# lampuIOT.net
KiCad netlist of a schematic drawn in EAGLE
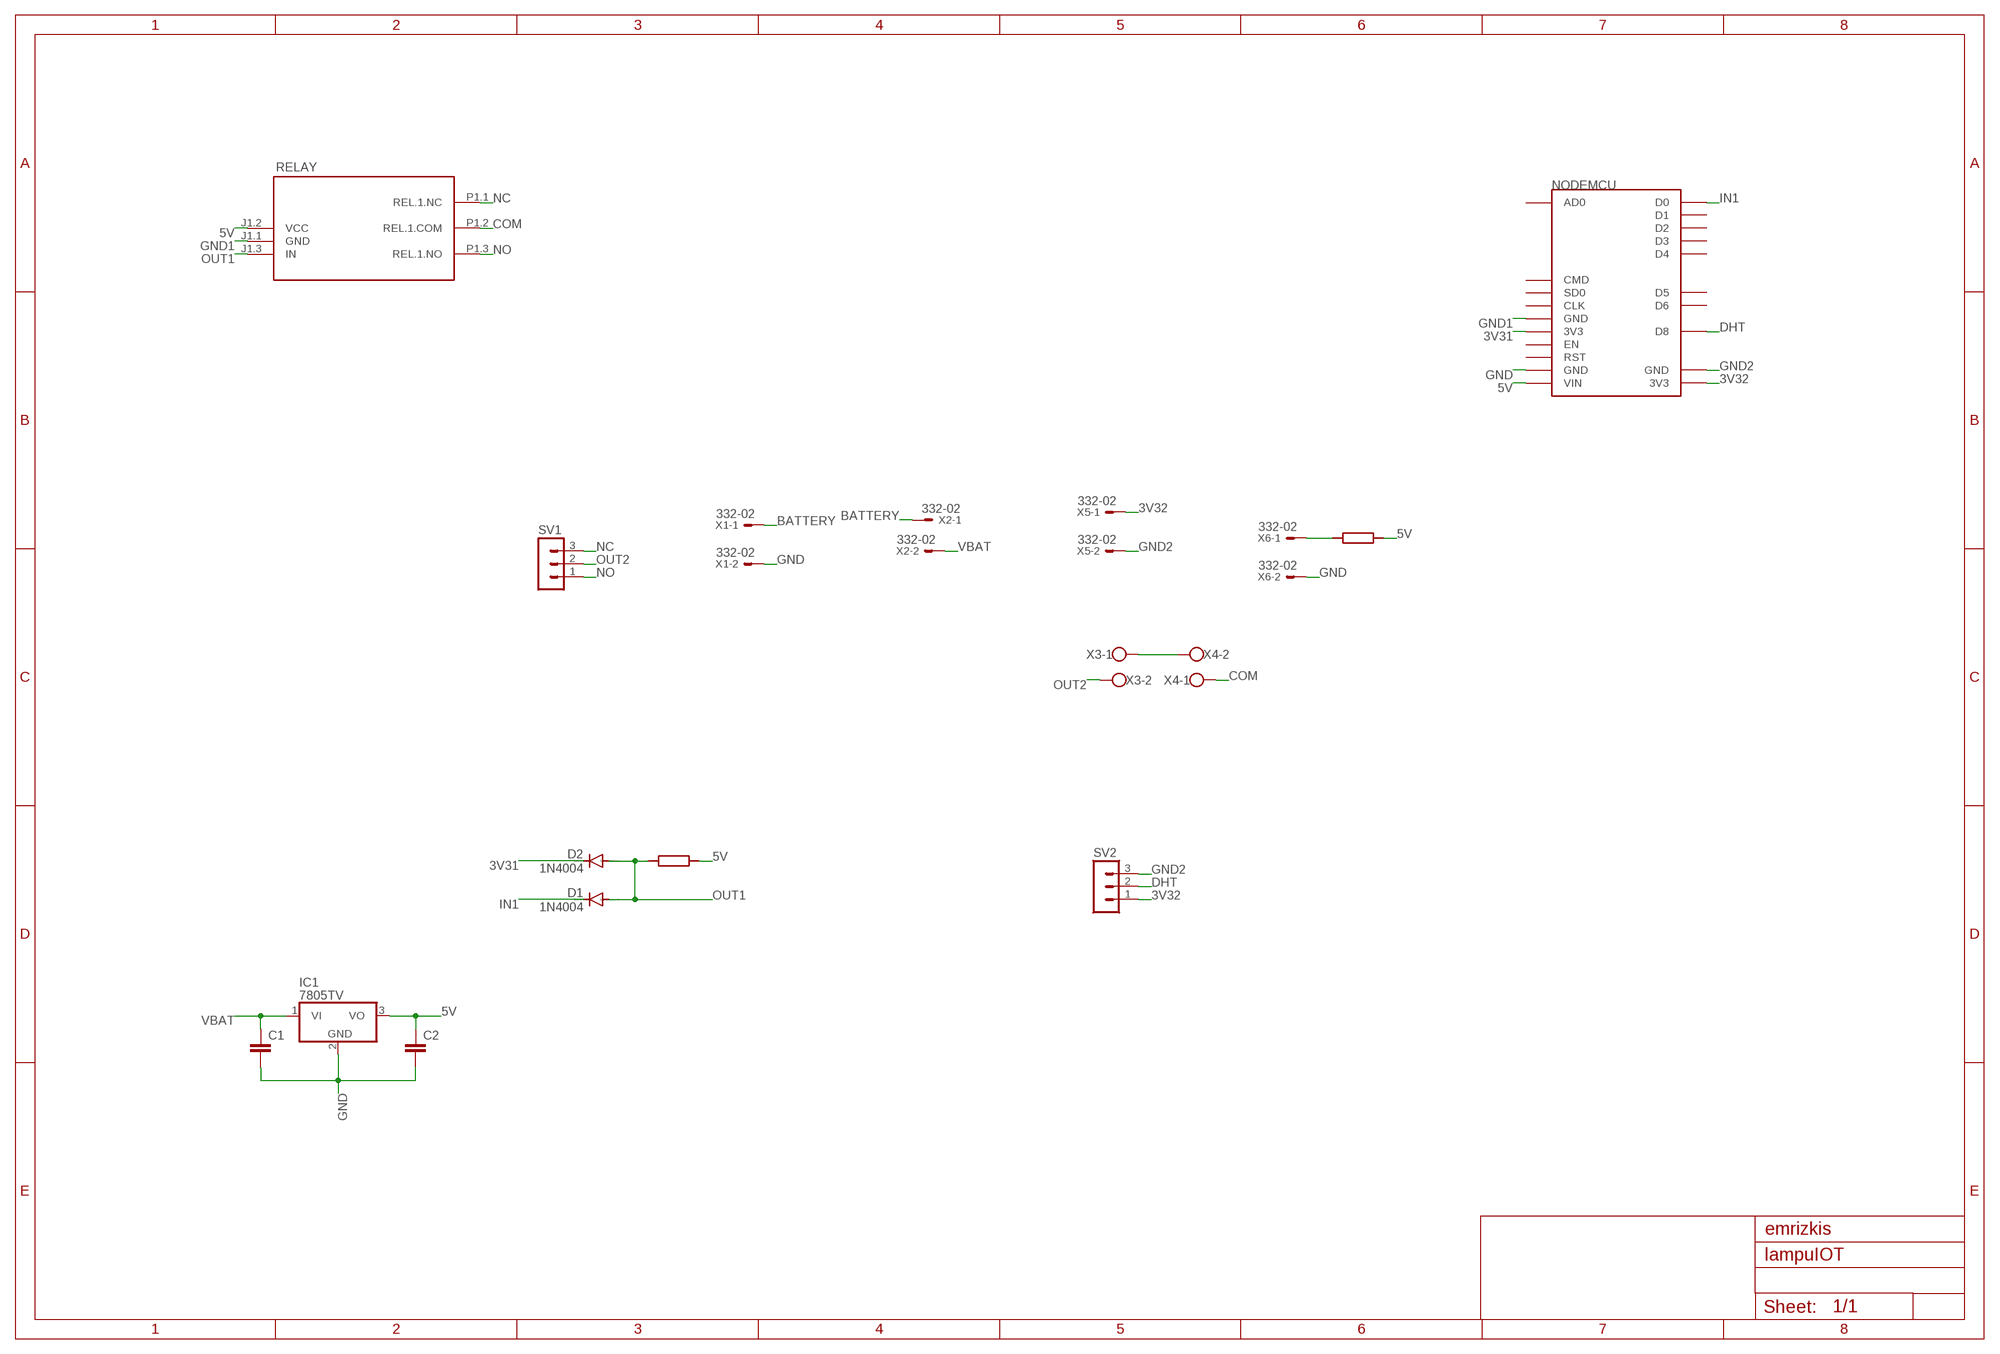
[diagram p0: schematic, sheet 1]

(export (version "E")
  (design (tool "Eeschema 10.0.6"))
  (components
    (comp (ref "C1")
      (value "C2.5/2")
      (footprint "eagle-import:C2.5-2")
      (libsource (lib "eagle-import") (part "C2.5/2"))
    )
    (comp (ref "C2")
      (value "C2.5/2")
      (footprint "eagle-import:C2.5-2")
      (libsource (lib "eagle-import") (part "C2.5/2"))
    )
    (comp (ref "D1")
      (value "1N4004")
      (footprint "eagle-import:DO41-10")
      (libsource (lib "eagle-import") (part "1N4004"))
    )
    (comp (ref "D2")
      (value "1N4004")
      (footprint "eagle-import:DO41-10")
      (libsource (lib "eagle-import") (part "1N4004"))
    )
    (comp (ref "IC1")
      (value "7805TV")
      (footprint "eagle-import:TO220V")
      (libsource (lib "eagle-import") (part "78TV05"))
    )
    (comp (ref "NODEMCU")
      (value "ESP12E_DEVKIT")
      (footprint "eagle-import:ESP12E_DEVKIT")
      (libsource (lib "eagle-import") (part "ESP12E_DEVKIT"))
    )
    (comp (ref "R")
      (value "RESISTOR")
      (footprint "eagle-import:RESISTOR")
      (libsource (lib "eagle-import") (part "RESISTOR"))
    )
    (comp (ref "R1")
      (value "RESISTOR")
      (footprint "eagle-import:RESISTOR")
      (libsource (lib "eagle-import") (part "RESISTOR"))
    )
    (comp (ref "RELAY")
      (value "RELAY1CH")
      (footprint "eagle-import:RELAY1CH")
      (libsource (lib "eagle-import") (part "RELAY1CH"))
    )
    (comp (ref "SV1")
      (value "MA03-1")
      (footprint "eagle-import:MA03-1")
      (libsource (lib "eagle-import") (part "MA03-1"))
    )
    (comp (ref "SV2")
      (value "MA03-1")
      (footprint "eagle-import:MA03-1")
      (libsource (lib "eagle-import") (part "MA03-1"))
    )
    (comp (ref "X1")
      (value "332-02")
      (footprint "eagle-import:332-02")
      (libsource (lib "eagle-import") (part "332-02"))
    )
    (comp (ref "X2")
      (value "332-02")
      (footprint "eagle-import:332-02")
      (libsource (lib "eagle-import") (part "332-02"))
    )
    (comp (ref "X3")
      (value "W237-102")
      (footprint "eagle-import:W237-102")
      (fields (field (name "MPN") "237-102"))
      (libsource (lib "eagle-import") (part "W237-102"))
    )
    (comp (ref "X4")
      (value "W237-102")
      (footprint "eagle-import:W237-102")
      (fields (field (name "MPN") "237-102"))
      (libsource (lib "eagle-import") (part "W237-102"))
    )
    (comp (ref "X5")
      (value "332-02")
      (footprint "eagle-import:332-02")
      (libsource (lib "eagle-import") (part "332-02"))
    )
    (comp (ref "X6")
      (value "332-02")
      (footprint "eagle-import:332-02")
      (libsource (lib "eagle-import") (part "332-02"))
    )
  )
  (nets
    (net (code "1") (name "/3V31") (class "Default")
      (node (ref "D2") (pin "C") (pinfunction "C_C") (pintype "passive"))
      (node (ref "NODEMCU") (pin "3V3@0") (pinfunction "3V3_3V3@0") (pintype "bidirectional"))
    )
    (net (code "2") (name "/3V32") (class "Default")
      (node (ref "NODEMCU") (pin "3V3@2") (pinfunction "3V3_3V3@2") (pintype "bidirectional"))
      (node (ref "SV2") (pin "1") (pinfunction "1_1") (pintype "passive"))
      (node (ref "X5") (pin "1") (pinfunction "S_1") (pintype "passive"))
    )
    (net (code "3") (name "/5V") (class "Default")
      (node (ref "C2") (pin "1") (pinfunction "1_1") (pintype "passive"))
      (node (ref "IC1") (pin "3") (pinfunction "VO_3") (pintype "passive"))
      (node (ref "NODEMCU") (pin "VIN") (pinfunction "VIN_VIN") (pintype "bidirectional"))
      (node (ref "R") (pin "P$1") (pinfunction "1_P$1") (pintype "input"))
      (node (ref "R1") (pin "P$1") (pinfunction "1_P$1") (pintype "input"))
      (node (ref "RELAY") (pin "J1.2") (pinfunction "VCC_J1.2") (pintype "power_in"))
    )
    (net (code "4") (name "/BATTERY") (class "Default")
      (node (ref "X1") (pin "1") (pinfunction "S_1") (pintype "passive"))
      (node (ref "X2") (pin "1") (pinfunction "S_1") (pintype "passive"))
    )
    (net (code "5") (name "/COM") (class "Default")
      (node (ref "RELAY") (pin "P1.2") (pinfunction "REL.1.COM_P1.2") (pintype "bidirectional"))
      (node (ref "X4") (pin "1") (pinfunction "KL_1") (pintype "passive"))
    )
    (net (code "6") (name "/DHT") (class "Default")
      (node (ref "NODEMCU") (pin "D8") (pinfunction "D8_D8") (pintype "bidirectional"))
      (node (ref "SV2") (pin "2") (pinfunction "2_2") (pintype "passive"))
    )
    (net (code "7") (name "/GND") (class "Default")
      (node (ref "C1") (pin "2") (pinfunction "2_2") (pintype "passive"))
      (node (ref "C2") (pin "2") (pinfunction "2_2") (pintype "passive"))
      (node (ref "IC1") (pin "2") (pinfunction "GND_2") (pintype "passive"))
      (node (ref "NODEMCU") (pin "GND@1") (pinfunction "GND_GND@1") (pintype "bidirectional"))
      (node (ref "X1") (pin "2") (pinfunction "S_2") (pintype "passive"))
      (node (ref "X6") (pin "2") (pinfunction "S_2") (pintype "passive"))
    )
    (net (code "8") (name "/GND1") (class "Default")
      (node (ref "NODEMCU") (pin "GND@0") (pinfunction "GND_GND@0") (pintype "bidirectional"))
      (node (ref "RELAY") (pin "J1.1") (pinfunction "GND_J1.1") (pintype "bidirectional"))
    )
    (net (code "9") (name "/GND2") (class "Default")
      (node (ref "NODEMCU") (pin "GND@3") (pinfunction "GND_GND@3") (pintype "bidirectional"))
      (node (ref "SV2") (pin "3") (pinfunction "3_3") (pintype "passive"))
      (node (ref "X5") (pin "2") (pinfunction "S_2") (pintype "passive"))
    )
    (net (code "10") (name "/IN1") (class "Default")
      (node (ref "D1") (pin "C") (pinfunction "C_C") (pintype "passive"))
      (node (ref "NODEMCU") (pin "D0") (pinfunction "D0_D0") (pintype "bidirectional"))
    )
    (net (code "11") (name "/NC") (class "Default")
      (node (ref "RELAY") (pin "P1.1") (pinfunction "REL.1.NC_P1.1") (pintype "bidirectional"))
      (node (ref "SV1") (pin "3") (pinfunction "3_3") (pintype "passive"))
    )
    (net (code "12") (name "/NO") (class "Default")
      (node (ref "RELAY") (pin "P1.3") (pinfunction "REL.1.NO_P1.3") (pintype "bidirectional"))
      (node (ref "SV1") (pin "1") (pinfunction "1_1") (pintype "passive"))
    )
    (net (code "13") (name "/OUT1") (class "Default")
      (node (ref "D1") (pin "A") (pinfunction "A_A") (pintype "passive"))
      (node (ref "D2") (pin "A") (pinfunction "A_A") (pintype "passive"))
      (node (ref "R") (pin "P$2") (pinfunction "2_P$2") (pintype "input"))
      (node (ref "RELAY") (pin "J1.3") (pinfunction "IN_J1.3") (pintype "power_in"))
    )
    (net (code "14") (name "/OUT2") (class "Default")
      (node (ref "SV1") (pin "2") (pinfunction "2_2") (pintype "passive"))
      (node (ref "X3") (pin "2") (pinfunction "KL_2") (pintype "passive"))
    )
    (net (code "15") (name "/VBAT") (class "Default")
      (node (ref "C1") (pin "1") (pinfunction "1_1") (pintype "passive"))
      (node (ref "IC1") (pin "1") (pinfunction "VI_1") (pintype "input"))
      (node (ref "X2") (pin "2") (pinfunction "S_2") (pintype "passive"))
    )
    (net (code "16") (name "Net-(R1-2)") (class "Default")
      (node (ref "R1") (pin "P$2") (pinfunction "2_P$2") (pintype "input"))
      (node (ref "X6") (pin "1") (pinfunction "S_1") (pintype "passive"))
    )
    (net (code "17") (name "Net-(X3A-KL)") (class "Default")
      (node (ref "X3") (pin "1") (pinfunction "KL_1") (pintype "passive"))
      (node (ref "X4") (pin "2") (pinfunction "KL_2") (pintype "passive"))
    )
    (net (code "18") (name "unconnected-(NODEMCU-PadAD0)") (class "Default")
      (node (ref "NODEMCU") (pin "AD0") (pinfunction "AD0_AD0") (pintype "bidirectional"))
    )
    (net (code "19") (name "unconnected-(NODEMCU-PadCLK)") (class "Default")
      (node (ref "NODEMCU") (pin "CLK") (pinfunction "CLK_CLK") (pintype "bidirectional"))
    )
    (net (code "20") (name "unconnected-(NODEMCU-PadCMD)") (class "Default")
      (node (ref "NODEMCU") (pin "CMD") (pinfunction "CMD_CMD") (pintype "bidirectional"))
    )
    (net (code "21") (name "unconnected-(NODEMCU-PadD1)") (class "Default")
      (node (ref "NODEMCU") (pin "D1") (pinfunction "D1_D1") (pintype "bidirectional"))
    )
    (net (code "22") (name "unconnected-(NODEMCU-PadD2)") (class "Default")
      (node (ref "NODEMCU") (pin "D2") (pinfunction "D2_D2") (pintype "bidirectional"))
    )
    (net (code "23") (name "unconnected-(NODEMCU-PadD3)") (class "Default")
      (node (ref "NODEMCU") (pin "D3") (pinfunction "D3_D3") (pintype "bidirectional"))
    )
    (net (code "24") (name "unconnected-(NODEMCU-PadD4)") (class "Default")
      (node (ref "NODEMCU") (pin "D4") (pinfunction "D4_D4") (pintype "bidirectional"))
    )
    (net (code "25") (name "unconnected-(NODEMCU-PadD5)") (class "Default")
      (node (ref "NODEMCU") (pin "D5") (pinfunction "D5_D5") (pintype "bidirectional"))
    )
    (net (code "26") (name "unconnected-(NODEMCU-PadD6)") (class "Default")
      (node (ref "NODEMCU") (pin "D6") (pinfunction "D6_D6") (pintype "bidirectional"))
    )
    (net (code "27") (name "unconnected-(NODEMCU-PadEN)") (class "Default")
      (node (ref "NODEMCU") (pin "EN") (pinfunction "EN_EN") (pintype "bidirectional"))
    )
    (net (code "28") (name "unconnected-(NODEMCU-PadRST)") (class "Default")
      (node (ref "NODEMCU") (pin "RST") (pinfunction "RST_RST") (pintype "bidirectional"))
    )
    (net (code "29") (name "unconnected-(NODEMCU-PadSD0)") (class "Default")
      (node (ref "NODEMCU") (pin "SD0") (pinfunction "SD0_SD0") (pintype "bidirectional"))
    )
  )
)
